# Rover_Sensors_Shield.net
KiCad netlist of a schematic drawn in EAGLE
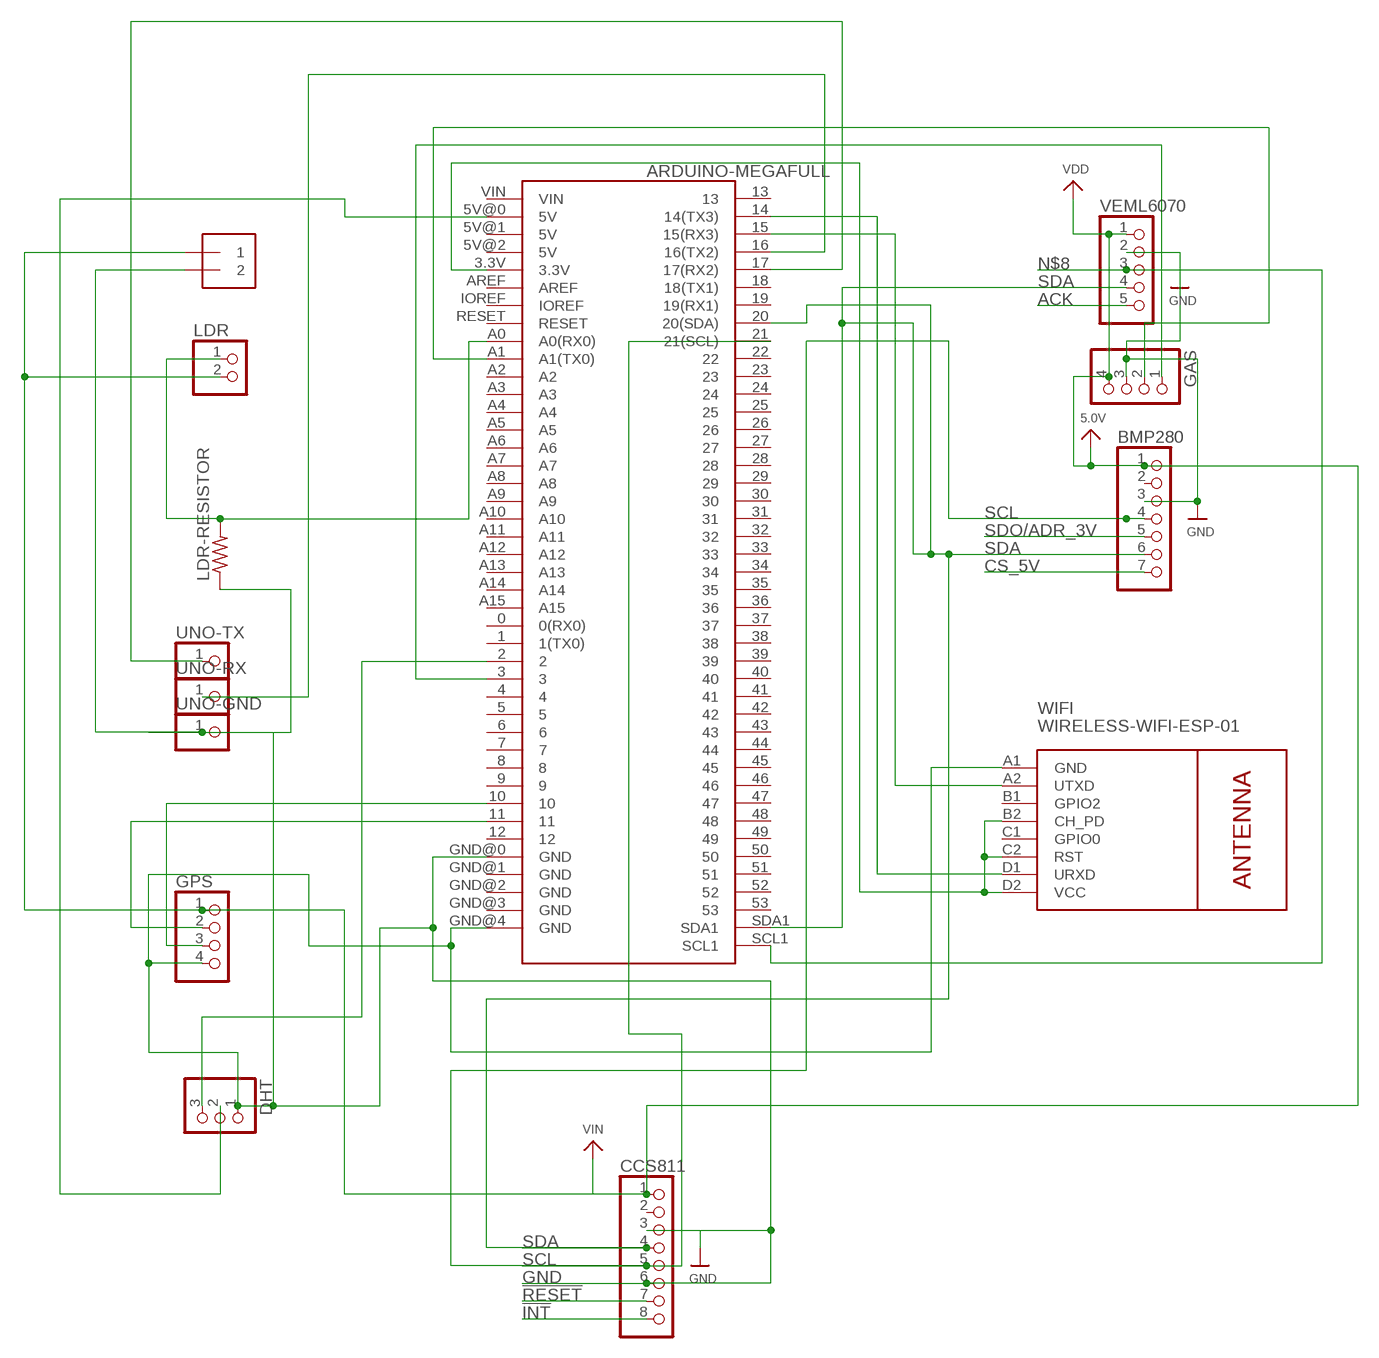
[diagram p0: schematic, sheet 1]

(export (version "E")
  (design (tool "Eeschema 10.0.6"))
  (components
    (comp (ref "BATTERY")
      (value "1X2-3.5MM")
      (footprint "eagle-import:1X2-3.5MM")
      (libsource (lib "eagle-import") (part "1X2-3.5MM"))
    )
    (comp (ref "BMP280")
      (value "HEADER-1X770MIL")
      (footprint "eagle-import:1X07_ROUND_70")
      (libsource (lib "eagle-import") (part "HEADER-1X770MIL"))
    )
    (comp (ref "CCS811")
      (value "HEADER-1X870MIL")
      (footprint "eagle-import:1X08_ROUND_70")
      (libsource (lib "eagle-import") (part "HEADER-1X870MIL"))
    )
    (comp (ref "DHT")
      (value "PINHD-1X3")
      (footprint "eagle-import:1X03")
      (libsource (lib "eagle-import") (part "PINHD-1X3"))
    )
    (comp (ref "GAS")
      (value "PINHD-1X4")
      (footprint "eagle-import:1X04")
      (libsource (lib "eagle-import") (part "PINHD-1X4"))
    )
    (comp (ref "GPS")
      (value "PINHD-1X4")
      (footprint "eagle-import:1X04")
      (libsource (lib "eagle-import") (part "PINHD-1X4"))
    )
    (comp (ref "LDR")
      (value "PINHD-1X2")
      (footprint "eagle-import:1X02")
      (libsource (lib "eagle-import") (part "PINHD-1X2"))
    )
    (comp (ref "LDR-RESISTOR")
      (value "R-US_0204/7")
      (footprint "eagle-import:0204_7")
      (libsource (lib "eagle-import") (part "R-US_0204/7"))
    )
    (comp (ref "U2")
      (value "ARDUINO-MEGAFULL")
      (footprint "eagle-import:ARDUINO_MEGA")
      (libsource (lib "eagle-import") (part "ARDUINO-MEGAFULL"))
    )
    (comp (ref "UNO-GND")
      (value "PINHD-1X1")
      (footprint "eagle-import:1X01")
      (libsource (lib "eagle-import") (part "PINHD-1X1"))
    )
    (comp (ref "UNO-RX")
      (value "PINHD-1X1")
      (footprint "eagle-import:1X01")
      (libsource (lib "eagle-import") (part "PINHD-1X1"))
    )
    (comp (ref "UNO-TX")
      (value "PINHD-1X1")
      (footprint "eagle-import:1X01")
      (libsource (lib "eagle-import") (part "PINHD-1X1"))
    )
    (comp (ref "VEML6070")
      (value "HEADER-1X570MIL")
      (footprint "eagle-import:1X05_ROUND_70")
      (libsource (lib "eagle-import") (part "HEADER-1X570MIL"))
    )
    (comp (ref "WIFI")
      (value "WIRELESS-WIFI-ESP-01")
      (footprint "eagle-import:WIRELESS-WIFI-ESP-01")
      (libsource (lib "eagle-import") (part "WIRELESS-WIFI-ESP-01"))
    )
  )
  (nets
    (net (code "1") (name "/ACK") (class "Default")
      (node (ref "VEML6070") (pin "5") (pinfunction "5_5") (pintype "passive"))
    )
    (net (code "2") (name "/CS_5V") (class "Default")
      (node (ref "BMP280") (pin "7") (pinfunction "7_7") (pintype "passive"))
    )
    (net (code "3") (name "/N$8") (class "Default")
      (node (ref "U2") (pin "SCL1") (pinfunction "SCL1_SCL1") (pintype "bidirectional"))
      (node (ref "VEML6070") (pin "3") (pinfunction "3_3") (pintype "passive"))
    )
    (net (code "4") (name "/SCL") (class "Default")
      (node (ref "BMP280") (pin "4") (pinfunction "4_4") (pintype "passive"))
      (node (ref "CCS811") (pin "5") (pinfunction "5_5") (pintype "passive"))
      (node (ref "U2") (pin "21") (pinfunction "21(SCL)_21") (pintype "bidirectional"))
    )
    (net (code "5") (name "/SDA") (class "Default")
      (node (ref "BMP280") (pin "6") (pinfunction "6_6") (pintype "passive"))
      (node (ref "CCS811") (pin "4") (pinfunction "4_4") (pintype "passive"))
      (node (ref "U2") (pin "20") (pinfunction "20(SDA)_20") (pintype "bidirectional"))
      (node (ref "U2") (pin "SDA1") (pinfunction "SDA1_SDA1") (pintype "bidirectional"))
      (node (ref "VEML6070") (pin "4") (pinfunction "4_4") (pintype "passive"))
    )
    (net (code "6") (name "/SDO{slash}ADR_3V") (class "Default")
      (node (ref "BMP280") (pin "5") (pinfunction "5_5") (pintype "passive"))
    )
    (net (code "7") (name "/~{INT}") (class "Default")
      (node (ref "CCS811") (pin "8") (pinfunction "8_8") (pintype "passive"))
    )
    (net (code "8") (name "/~{RESET}") (class "Default")
      (node (ref "CCS811") (pin "7") (pinfunction "7_7") (pintype "passive"))
    )
    (net (code "9") (name "5.0V") (class "Default")
      (node (ref "BATTERY") (pin "1") (pinfunction "1_1") (pintype "passive"))
      (node (ref "BMP280") (pin "1") (pinfunction "1_1") (pintype "passive"))
      (node (ref "CCS811") (pin "1") (pinfunction "1_1") (pintype "passive"))
      (node (ref "GAS") (pin "4") (pinfunction "4_4") (pintype "passive"))
      (node (ref "GPS") (pin "1") (pinfunction "1_1") (pintype "passive"))
      (node (ref "LDR") (pin "2") (pinfunction "2_2") (pintype "passive"))
      (node (ref "VEML6070") (pin "1") (pinfunction "1_1") (pintype "passive"))
    )
    (net (code "10") (name "GND") (class "Default")
      (node (ref "BATTERY") (pin "2") (pinfunction "2_2") (pintype "passive"))
      (node (ref "BMP280") (pin "3") (pinfunction "3_3") (pintype "passive"))
      (node (ref "CCS811") (pin "3") (pinfunction "3_3") (pintype "passive"))
      (node (ref "CCS811") (pin "6") (pinfunction "6_6") (pintype "passive"))
      (node (ref "DHT") (pin "1") (pinfunction "1_1") (pintype "passive"))
      (node (ref "GAS") (pin "3") (pinfunction "3_3") (pintype "passive"))
      (node (ref "GPS") (pin "4") (pinfunction "4_4") (pintype "passive"))
      (node (ref "LDR-RESISTOR") (pin "1") (pinfunction "1_1") (pintype "passive"))
      (node (ref "U2") (pin "GND@0") (pinfunction "GND_GND@0") (pintype "bidirectional"))
      (node (ref "U2") (pin "GND@4") (pinfunction "GND_GND@4") (pintype "bidirectional"))
      (node (ref "UNO-GND") (pin "1") (pinfunction "1_1") (pintype "passive"))
      (node (ref "VEML6070") (pin "2") (pinfunction "2_2") (pintype "passive"))
      (node (ref "WIFI") (pin "A1") (pinfunction "GND_A1") (pintype "power_in"))
    )
    (net (code "11") (name "Net-(DHT-Pad2)") (class "Default")
      (node (ref "DHT") (pin "2") (pinfunction "2_2") (pintype "passive"))
      (node (ref "U2") (pin "5V@0") (pinfunction "5V_5V@0") (pintype "bidirectional"))
    )
    (net (code "12") (name "Net-(DHT-Pad3)") (class "Default")
      (node (ref "DHT") (pin "3") (pinfunction "3_3") (pintype "passive"))
      (node (ref "U2") (pin "2") (pinfunction "2_2") (pintype "bidirectional"))
    )
    (net (code "13") (name "Net-(GAS-Pad1)") (class "Default")
      (node (ref "GAS") (pin "1") (pinfunction "1_1") (pintype "passive"))
      (node (ref "U2") (pin "3") (pinfunction "3_3") (pintype "bidirectional"))
    )
    (net (code "14") (name "Net-(GPS-Pad2)") (class "Default")
      (node (ref "GPS") (pin "2") (pinfunction "2_2") (pintype "passive"))
      (node (ref "U2") (pin "11") (pinfunction "11_11") (pintype "bidirectional"))
    )
    (net (code "15") (name "Net-(GPS-Pad3)") (class "Default")
      (node (ref "GPS") (pin "3") (pinfunction "3_3") (pintype "passive"))
      (node (ref "U2") (pin "10") (pinfunction "10_10") (pintype "bidirectional"))
    )
    (net (code "16") (name "Net-(U2-14(TX3))") (class "Default")
      (node (ref "U2") (pin "14") (pinfunction "14(TX3)_14") (pintype "bidirectional"))
      (node (ref "WIFI") (pin "D1") (pinfunction "URXD_D1") (pintype "bidirectional"))
    )
    (net (code "17") (name "Net-(U2-15(RX3))") (class "Default")
      (node (ref "U2") (pin "15") (pinfunction "15(RX3)_15") (pintype "bidirectional"))
      (node (ref "WIFI") (pin "A2") (pinfunction "UTXD_A2") (pintype "bidirectional"))
    )
    (net (code "18") (name "Net-(U2-16(TX2))") (class "Default")
      (node (ref "U2") (pin "16") (pinfunction "16(TX2)_16") (pintype "bidirectional"))
      (node (ref "UNO-RX") (pin "1") (pinfunction "1_1") (pintype "passive"))
    )
    (net (code "19") (name "Net-(U2-17(RX2))") (class "Default")
      (node (ref "U2") (pin "17") (pinfunction "17(RX2)_17") (pintype "bidirectional"))
      (node (ref "UNO-TX") (pin "1") (pinfunction "1_1") (pintype "passive"))
    )
    (net (code "20") (name "Net-(U2-A0(RX0))") (class "Default")
      (node (ref "LDR") (pin "1") (pinfunction "1_1") (pintype "passive"))
      (node (ref "LDR-RESISTOR") (pin "2") (pinfunction "2_2") (pintype "passive"))
      (node (ref "U2") (pin "A0") (pinfunction "A0(RX0)_A0") (pintype "bidirectional"))
    )
    (net (code "21") (name "Net-(U2-A1(TX0))") (class "Default")
      (node (ref "GAS") (pin "2") (pinfunction "2_2") (pintype "passive"))
      (node (ref "U2") (pin "A1") (pinfunction "A1(TX0)_A1") (pintype "bidirectional"))
    )
    (net (code "22") (name "Net-(WIFI-CH_PD)") (class "Default")
      (node (ref "U2") (pin "3.3V") (pinfunction "3.3V_3.3V") (pintype "bidirectional"))
      (node (ref "WIFI") (pin "B2") (pinfunction "CH_PD_B2") (pintype "bidirectional"))
      (node (ref "WIFI") (pin "C2") (pinfunction "RST_C2") (pintype "bidirectional"))
      (node (ref "WIFI") (pin "D2") (pinfunction "VCC_D2") (pintype "power_in"))
    )
    (net (code "23") (name "unconnected-(BMP280-Pad2)") (class "Default")
      (node (ref "BMP280") (pin "2") (pinfunction "2_2") (pintype "passive"))
    )
    (net (code "24") (name "unconnected-(CCS811-Pad2)") (class "Default")
      (node (ref "CCS811") (pin "2") (pinfunction "2_2") (pintype "passive"))
    )
    (net (code "25") (name "unconnected-(U2-0(RX0)-Pad0)") (class "Default")
      (node (ref "U2") (pin "0") (pinfunction "0(RX0)_0") (pintype "bidirectional"))
    )
    (net (code "26") (name "unconnected-(U2-1(TX0)-Pad1)") (class "Default")
      (node (ref "U2") (pin "1") (pinfunction "1(TX0)_1") (pintype "bidirectional"))
    )
    (net (code "27") (name "unconnected-(U2-5V-Pad5V@1)") (class "Default")
      (node (ref "U2") (pin "5V@1") (pinfunction "5V_5V@1") (pintype "bidirectional"))
    )
    (net (code "28") (name "unconnected-(U2-5V-Pad5V@2)") (class "Default")
      (node (ref "U2") (pin "5V@2") (pinfunction "5V_5V@2") (pintype "bidirectional"))
    )
    (net (code "29") (name "unconnected-(U2-18(TX1)-Pad18)") (class "Default")
      (node (ref "U2") (pin "18") (pinfunction "18(TX1)_18") (pintype "bidirectional"))
    )
    (net (code "30") (name "unconnected-(U2-19(RX1)-Pad19)") (class "Default")
      (node (ref "U2") (pin "19") (pinfunction "19(RX1)_19") (pintype "bidirectional"))
    )
    (net (code "31") (name "unconnected-(U2-GND-PadGND@1)") (class "Default")
      (node (ref "U2") (pin "GND@1") (pinfunction "GND_GND@1") (pintype "bidirectional"))
    )
    (net (code "32") (name "unconnected-(U2-GND-PadGND@2)") (class "Default")
      (node (ref "U2") (pin "GND@2") (pinfunction "GND_GND@2") (pintype "bidirectional"))
    )
    (net (code "33") (name "unconnected-(U2-GND-PadGND@3)") (class "Default")
      (node (ref "U2") (pin "GND@3") (pinfunction "GND_GND@3") (pintype "bidirectional"))
    )
    (net (code "34") (name "unconnected-(U2-Pad4)") (class "Default")
      (node (ref "U2") (pin "4") (pinfunction "4_4") (pintype "bidirectional"))
    )
    (net (code "35") (name "unconnected-(U2-Pad5)") (class "Default")
      (node (ref "U2") (pin "5") (pinfunction "5_5") (pintype "bidirectional"))
    )
    (net (code "36") (name "unconnected-(U2-Pad6)") (class "Default")
      (node (ref "U2") (pin "6") (pinfunction "6_6") (pintype "bidirectional"))
    )
    (net (code "37") (name "unconnected-(U2-Pad7)") (class "Default")
      (node (ref "U2") (pin "7") (pinfunction "7_7") (pintype "bidirectional"))
    )
    (net (code "38") (name "unconnected-(U2-Pad8)") (class "Default")
      (node (ref "U2") (pin "8") (pinfunction "8_8") (pintype "bidirectional"))
    )
    (net (code "39") (name "unconnected-(U2-Pad9)") (class "Default")
      (node (ref "U2") (pin "9") (pinfunction "9_9") (pintype "bidirectional"))
    )
    (net (code "40") (name "unconnected-(U2-Pad12)") (class "Default")
      (node (ref "U2") (pin "12") (pinfunction "12_12") (pintype "bidirectional"))
    )
    (net (code "41") (name "unconnected-(U2-Pad13)") (class "Default")
      (node (ref "U2") (pin "13") (pinfunction "13_13") (pintype "bidirectional"))
    )
    (net (code "42") (name "unconnected-(U2-Pad22)") (class "Default")
      (node (ref "U2") (pin "22") (pinfunction "22_22") (pintype "bidirectional"))
    )
    (net (code "43") (name "unconnected-(U2-Pad23)") (class "Default")
      (node (ref "U2") (pin "23") (pinfunction "23_23") (pintype "bidirectional"))
    )
    (net (code "44") (name "unconnected-(U2-Pad24)") (class "Default")
      (node (ref "U2") (pin "24") (pinfunction "24_24") (pintype "bidirectional"))
    )
    (net (code "45") (name "unconnected-(U2-Pad25)") (class "Default")
      (node (ref "U2") (pin "25") (pinfunction "25_25") (pintype "bidirectional"))
    )
    (net (code "46") (name "unconnected-(U2-Pad26)") (class "Default")
      (node (ref "U2") (pin "26") (pinfunction "26_26") (pintype "bidirectional"))
    )
    (net (code "47") (name "unconnected-(U2-Pad27)") (class "Default")
      (node (ref "U2") (pin "27") (pinfunction "27_27") (pintype "bidirectional"))
    )
    (net (code "48") (name "unconnected-(U2-Pad28)") (class "Default")
      (node (ref "U2") (pin "28") (pinfunction "28_28") (pintype "bidirectional"))
    )
    (net (code "49") (name "unconnected-(U2-Pad29)") (class "Default")
      (node (ref "U2") (pin "29") (pinfunction "29_29") (pintype "bidirectional"))
    )
    (net (code "50") (name "unconnected-(U2-Pad30)") (class "Default")
      (node (ref "U2") (pin "30") (pinfunction "30_30") (pintype "bidirectional"))
    )
    (net (code "51") (name "unconnected-(U2-Pad31)") (class "Default")
      (node (ref "U2") (pin "31") (pinfunction "31_31") (pintype "bidirectional"))
    )
    (net (code "52") (name "unconnected-(U2-Pad32)") (class "Default")
      (node (ref "U2") (pin "32") (pinfunction "32_32") (pintype "bidirectional"))
    )
    (net (code "53") (name "unconnected-(U2-Pad33)") (class "Default")
      (node (ref "U2") (pin "33") (pinfunction "33_33") (pintype "bidirectional"))
    )
    (net (code "54") (name "unconnected-(U2-Pad34)") (class "Default")
      (node (ref "U2") (pin "34") (pinfunction "34_34") (pintype "bidirectional"))
    )
    (net (code "55") (name "unconnected-(U2-Pad35)") (class "Default")
      (node (ref "U2") (pin "35") (pinfunction "35_35") (pintype "bidirectional"))
    )
    (net (code "56") (name "unconnected-(U2-Pad36)") (class "Default")
      (node (ref "U2") (pin "36") (pinfunction "36_36") (pintype "bidirectional"))
    )
    (net (code "57") (name "unconnected-(U2-Pad37)") (class "Default")
      (node (ref "U2") (pin "37") (pinfunction "37_37") (pintype "bidirectional"))
    )
    (net (code "58") (name "unconnected-(U2-Pad38)") (class "Default")
      (node (ref "U2") (pin "38") (pinfunction "38_38") (pintype "bidirectional"))
    )
    (net (code "59") (name "unconnected-(U2-Pad39)") (class "Default")
      (node (ref "U2") (pin "39") (pinfunction "39_39") (pintype "bidirectional"))
    )
    (net (code "60") (name "unconnected-(U2-Pad40)") (class "Default")
      (node (ref "U2") (pin "40") (pinfunction "40_40") (pintype "bidirectional"))
    )
    (net (code "61") (name "unconnected-(U2-Pad41)") (class "Default")
      (node (ref "U2") (pin "41") (pinfunction "41_41") (pintype "bidirectional"))
    )
    (net (code "62") (name "unconnected-(U2-Pad42)") (class "Default")
      (node (ref "U2") (pin "42") (pinfunction "42_42") (pintype "bidirectional"))
    )
    (net (code "63") (name "unconnected-(U2-Pad43)") (class "Default")
      (node (ref "U2") (pin "43") (pinfunction "43_43") (pintype "bidirectional"))
    )
    (net (code "64") (name "unconnected-(U2-Pad44)") (class "Default")
      (node (ref "U2") (pin "44") (pinfunction "44_44") (pintype "bidirectional"))
    )
    (net (code "65") (name "unconnected-(U2-Pad45)") (class "Default")
      (node (ref "U2") (pin "45") (pinfunction "45_45") (pintype "bidirectional"))
    )
    (net (code "66") (name "unconnected-(U2-Pad46)") (class "Default")
      (node (ref "U2") (pin "46") (pinfunction "46_46") (pintype "bidirectional"))
    )
    (net (code "67") (name "unconnected-(U2-Pad47)") (class "Default")
      (node (ref "U2") (pin "47") (pinfunction "47_47") (pintype "bidirectional"))
    )
    (net (code "68") (name "unconnected-(U2-Pad48)") (class "Default")
      (node (ref "U2") (pin "48") (pinfunction "48_48") (pintype "bidirectional"))
    )
    (net (code "69") (name "unconnected-(U2-Pad49)") (class "Default")
      (node (ref "U2") (pin "49") (pinfunction "49_49") (pintype "bidirectional"))
    )
    (net (code "70") (name "unconnected-(U2-Pad50)") (class "Default")
      (node (ref "U2") (pin "50") (pinfunction "50_50") (pintype "bidirectional"))
    )
    (net (code "71") (name "unconnected-(U2-Pad51)") (class "Default")
      (node (ref "U2") (pin "51") (pinfunction "51_51") (pintype "bidirectional"))
    )
    (net (code "72") (name "unconnected-(U2-Pad52)") (class "Default")
      (node (ref "U2") (pin "52") (pinfunction "52_52") (pintype "bidirectional"))
    )
    (net (code "73") (name "unconnected-(U2-Pad53)") (class "Default")
      (node (ref "U2") (pin "53") (pinfunction "53_53") (pintype "bidirectional"))
    )
    (net (code "74") (name "unconnected-(U2-PadA2)") (class "Default")
      (node (ref "U2") (pin "A2") (pinfunction "A2_A2") (pintype "bidirectional"))
    )
    (net (code "75") (name "unconnected-(U2-PadA3)") (class "Default")
      (node (ref "U2") (pin "A3") (pinfunction "A3_A3") (pintype "bidirectional"))
    )
    (net (code "76") (name "unconnected-(U2-PadA4)") (class "Default")
      (node (ref "U2") (pin "A4") (pinfunction "A4_A4") (pintype "bidirectional"))
    )
    (net (code "77") (name "unconnected-(U2-PadA5)") (class "Default")
      (node (ref "U2") (pin "A5") (pinfunction "A5_A5") (pintype "bidirectional"))
    )
    (net (code "78") (name "unconnected-(U2-PadA6)") (class "Default")
      (node (ref "U2") (pin "A6") (pinfunction "A6_A6") (pintype "bidirectional"))
    )
    (net (code "79") (name "unconnected-(U2-PadA7)") (class "Default")
      (node (ref "U2") (pin "A7") (pinfunction "A7_A7") (pintype "bidirectional"))
    )
    (net (code "80") (name "unconnected-(U2-PadA8)") (class "Default")
      (node (ref "U2") (pin "A8") (pinfunction "A8_A8") (pintype "bidirectional"))
    )
    (net (code "81") (name "unconnected-(U2-PadA9)") (class "Default")
      (node (ref "U2") (pin "A9") (pinfunction "A9_A9") (pintype "bidirectional"))
    )
    (net (code "82") (name "unconnected-(U2-PadA10)") (class "Default")
      (node (ref "U2") (pin "A10") (pinfunction "A10_A10") (pintype "bidirectional"))
    )
    (net (code "83") (name "unconnected-(U2-PadA11)") (class "Default")
      (node (ref "U2") (pin "A11") (pinfunction "A11_A11") (pintype "bidirectional"))
    )
    (net (code "84") (name "unconnected-(U2-PadA12)") (class "Default")
      (node (ref "U2") (pin "A12") (pinfunction "A12_A12") (pintype "bidirectional"))
    )
    (net (code "85") (name "unconnected-(U2-PadA13)") (class "Default")
      (node (ref "U2") (pin "A13") (pinfunction "A13_A13") (pintype "bidirectional"))
    )
    (net (code "86") (name "unconnected-(U2-PadA14)") (class "Default")
      (node (ref "U2") (pin "A14") (pinfunction "A14_A14") (pintype "bidirectional"))
    )
    (net (code "87") (name "unconnected-(U2-PadA15)") (class "Default")
      (node (ref "U2") (pin "A15") (pinfunction "A15_A15") (pintype "bidirectional"))
    )
    (net (code "88") (name "unconnected-(U2-PadAREF)") (class "Default")
      (node (ref "U2") (pin "AREF") (pinfunction "AREF_AREF") (pintype "bidirectional"))
    )
    (net (code "89") (name "unconnected-(U2-PadIOREF)") (class "Default")
      (node (ref "U2") (pin "IOREF") (pinfunction "IOREF_IOREF") (pintype "bidirectional"))
    )
    (net (code "90") (name "unconnected-(U2-PadRESET)") (class "Default")
      (node (ref "U2") (pin "RESET") (pinfunction "RESET_RESET") (pintype "bidirectional"))
    )
    (net (code "91") (name "unconnected-(U2-PadVIN)") (class "Default")
      (node (ref "U2") (pin "VIN") (pinfunction "VIN_VIN") (pintype "bidirectional"))
    )
    (net (code "92") (name "unconnected-(WIFI-GPIO0-PadC1)") (class "Default")
      (node (ref "WIFI") (pin "C1") (pinfunction "GPIO0_C1") (pintype "bidirectional"))
    )
    (net (code "93") (name "unconnected-(WIFI-GPIO2-PadB1)") (class "Default")
      (node (ref "WIFI") (pin "B1") (pinfunction "GPIO2_B1") (pintype "bidirectional"))
    )
  )
)
